# PHOBOS-lbr.net
KiCad netlist of a schematic drawn in EAGLE
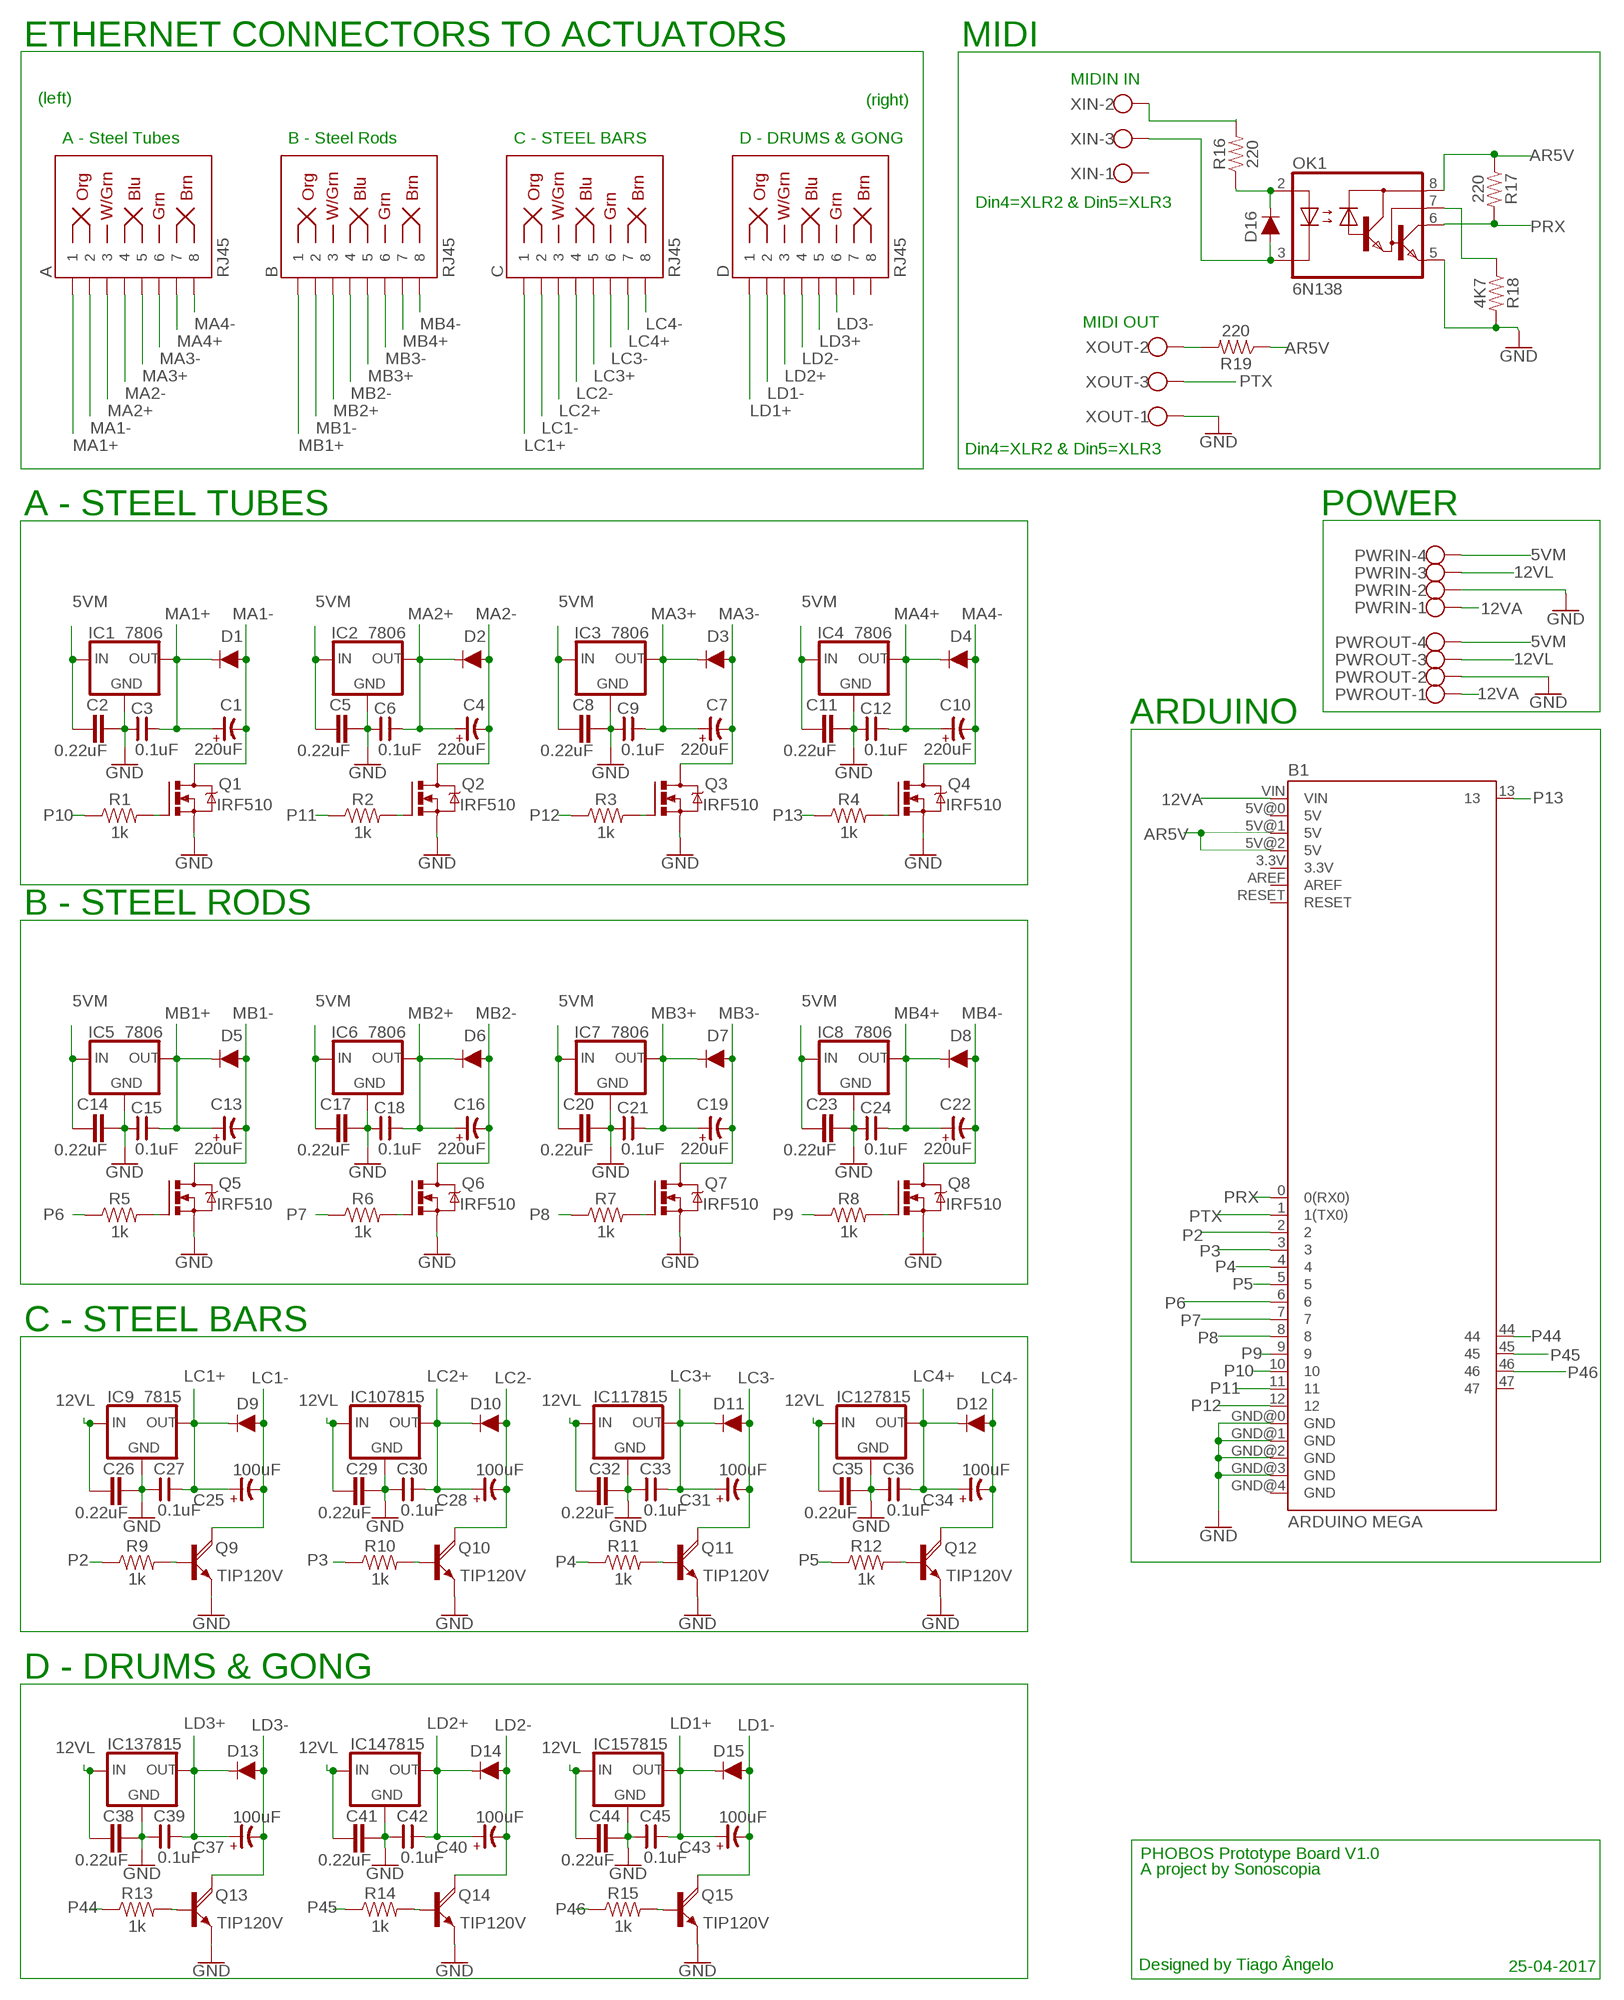
[diagram p0: schematic, sheet 1]

(export (version "E")
  (design (tool "Eeschema 10.0.6"))
  (components
    (comp (ref "A")
      (value "RJ45")
      (footprint "eagle-import:RJ45-8")
      (libsource (lib "eagle-import") (part "RJ45-8"))
    )
    (comp (ref "B")
      (value "RJ45")
      (footprint "eagle-import:RJ45-8")
      (libsource (lib "eagle-import") (part "RJ45-8"))
    )
    (comp (ref "B1")
      (value "ARDUINO MEGA")
      (footprint "eagle-import:ARDUINO_MEGA")
      (libsource (lib "eagle-import") (part "ARDUINO_MEGA_R3FULL"))
    )
    (comp (ref "C")
      (value "RJ45")
      (footprint "eagle-import:RJ45-8")
      (libsource (lib "eagle-import") (part "RJ45-8"))
    )
    (comp (ref "C1")
      (value "220uF")
      (footprint "eagle-import:E-035X080")
      (libsource (lib "eagle-import") (part "CP-E-035X080"))
    )
    (comp (ref "C2")
      (value "0.22uF")
      (footprint "eagle-import:C5B3")
      (libsource (lib "eagle-import") (part "C5/3"))
    )
    (comp (ref "C3")
      (value "0.1uF")
      (footprint "eagle-import:C025-050X025")
      (libsource (lib "eagle-import") (part "CNP-C025-050X025"))
    )
    (comp (ref "C4")
      (value "220uF")
      (footprint "eagle-import:E-035X080")
      (libsource (lib "eagle-import") (part "CP-E-035X080"))
    )
    (comp (ref "C5")
      (value "0.22uF")
      (footprint "eagle-import:C5B3")
      (libsource (lib "eagle-import") (part "C5/3"))
    )
    (comp (ref "C6")
      (value "0.1uF")
      (footprint "eagle-import:C025-050X025")
      (libsource (lib "eagle-import") (part "CNP-C025-050X025"))
    )
    (comp (ref "C7")
      (value "220uF")
      (footprint "eagle-import:E-035X080")
      (libsource (lib "eagle-import") (part "CP-E-035X080"))
    )
    (comp (ref "C8")
      (value "0.22uF")
      (footprint "eagle-import:C5B3")
      (libsource (lib "eagle-import") (part "C5/3"))
    )
    (comp (ref "C9")
      (value "0.1uF")
      (footprint "eagle-import:C025-050X025")
      (libsource (lib "eagle-import") (part "CNP-C025-050X025"))
    )
    (comp (ref "C10")
      (value "220uF")
      (footprint "eagle-import:E-035X080")
      (libsource (lib "eagle-import") (part "CP-E-035X080"))
    )
    (comp (ref "C11")
      (value "0.22uF")
      (footprint "eagle-import:C5B3")
      (libsource (lib "eagle-import") (part "C5/3"))
    )
    (comp (ref "C12")
      (value "0.1uF")
      (footprint "eagle-import:C025-050X025")
      (libsource (lib "eagle-import") (part "CNP-C025-050X025"))
    )
    (comp (ref "C13")
      (value "220uF")
      (footprint "eagle-import:E-035X080")
      (libsource (lib "eagle-import") (part "CP-E-035X080"))
    )
    (comp (ref "C14")
      (value "0.22uF")
      (footprint "eagle-import:C5B3")
      (libsource (lib "eagle-import") (part "C5/3"))
    )
    (comp (ref "C15")
      (value "0.1uF")
      (footprint "eagle-import:C025-050X025")
      (libsource (lib "eagle-import") (part "CNP-C025-050X025"))
    )
    (comp (ref "C16")
      (value "220uF")
      (footprint "eagle-import:E-035X080")
      (libsource (lib "eagle-import") (part "CP-E-035X080"))
    )
    (comp (ref "C17")
      (value "0.22uF")
      (footprint "eagle-import:C5B3")
      (libsource (lib "eagle-import") (part "C5/3"))
    )
    (comp (ref "C18")
      (value "0.1uF")
      (footprint "eagle-import:C025-050X025")
      (libsource (lib "eagle-import") (part "CNP-C025-050X025"))
    )
    (comp (ref "C19")
      (value "220uF")
      (footprint "eagle-import:E-035X080")
      (libsource (lib "eagle-import") (part "CP-E-035X080"))
    )
    (comp (ref "C20")
      (value "0.22uF")
      (footprint "eagle-import:C5B3")
      (libsource (lib "eagle-import") (part "C5/3"))
    )
    (comp (ref "C21")
      (value "0.1uF")
      (footprint "eagle-import:C025-050X025")
      (libsource (lib "eagle-import") (part "CNP-C025-050X025"))
    )
    (comp (ref "C22")
      (value "220uF")
      (footprint "eagle-import:E-035X080")
      (libsource (lib "eagle-import") (part "CP-E-035X080"))
    )
    (comp (ref "C23")
      (value "0.22uF")
      (footprint "eagle-import:C5B3")
      (libsource (lib "eagle-import") (part "C5/3"))
    )
    (comp (ref "C24")
      (value "0.1uF")
      (footprint "eagle-import:C025-050X025")
      (libsource (lib "eagle-import") (part "CNP-C025-050X025"))
    )
    (comp (ref "C25")
      (value "100uF")
      (footprint "eagle-import:E-020X050")
      (libsource (lib "eagle-import") (part "CP-E-020X050"))
    )
    (comp (ref "C26")
      (value "0.22uF")
      (footprint "eagle-import:C5B3")
      (libsource (lib "eagle-import") (part "C5/3"))
    )
    (comp (ref "C27")
      (value "0.1uF")
      (footprint "eagle-import:C025-050X025")
      (libsource (lib "eagle-import") (part "CNP-C025-050X025"))
    )
    (comp (ref "C28")
      (value "100uF")
      (footprint "eagle-import:E-020X050")
      (libsource (lib "eagle-import") (part "CP-E-020X050"))
    )
    (comp (ref "C29")
      (value "0.22uF")
      (footprint "eagle-import:C5B3")
      (libsource (lib "eagle-import") (part "C5/3"))
    )
    (comp (ref "C30")
      (value "0.1uF")
      (footprint "eagle-import:C025-050X025")
      (libsource (lib "eagle-import") (part "CNP-C025-050X025"))
    )
    (comp (ref "C31")
      (value "100uF")
      (footprint "eagle-import:E-020X050")
      (libsource (lib "eagle-import") (part "CP-E-020X050"))
    )
    (comp (ref "C32")
      (value "0.22uF")
      (footprint "eagle-import:C5B3")
      (libsource (lib "eagle-import") (part "C5/3"))
    )
    (comp (ref "C33")
      (value "0.1uF")
      (footprint "eagle-import:C025-050X025")
      (libsource (lib "eagle-import") (part "CNP-C025-050X025"))
    )
    (comp (ref "C34")
      (value "100uF")
      (footprint "eagle-import:E-020X050")
      (libsource (lib "eagle-import") (part "CP-E-020X050"))
    )
    (comp (ref "C35")
      (value "0.22uF")
      (footprint "eagle-import:C5B3")
      (libsource (lib "eagle-import") (part "C5/3"))
    )
    (comp (ref "C36")
      (value "0.1uF")
      (footprint "eagle-import:C025-050X025")
      (libsource (lib "eagle-import") (part "CNP-C025-050X025"))
    )
    (comp (ref "C37")
      (value "100uF")
      (footprint "eagle-import:E-020X050")
      (libsource (lib "eagle-import") (part "CP-E-020X050"))
    )
    (comp (ref "C38")
      (value "0.22uF")
      (footprint "eagle-import:C5B3")
      (libsource (lib "eagle-import") (part "C5/3"))
    )
    (comp (ref "C39")
      (value "0.1uF")
      (footprint "eagle-import:C025-050X025")
      (libsource (lib "eagle-import") (part "CNP-C025-050X025"))
    )
    (comp (ref "C40")
      (value "100uF")
      (footprint "eagle-import:E-020X050")
      (libsource (lib "eagle-import") (part "CP-E-020X050"))
    )
    (comp (ref "C41")
      (value "0.22uF")
      (footprint "eagle-import:C5B3")
      (libsource (lib "eagle-import") (part "C5/3"))
    )
    (comp (ref "C42")
      (value "0.1uF")
      (footprint "eagle-import:C025-050X025")
      (libsource (lib "eagle-import") (part "CNP-C025-050X025"))
    )
    (comp (ref "C43")
      (value "100uF")
      (footprint "eagle-import:E-020X050")
      (libsource (lib "eagle-import") (part "CP-E-020X050"))
    )
    (comp (ref "C44")
      (value "0.22uF")
      (footprint "eagle-import:C5B3")
      (libsource (lib "eagle-import") (part "C5/3"))
    )
    (comp (ref "C45")
      (value "0.1uF")
      (footprint "eagle-import:C025-050X025")
      (libsource (lib "eagle-import") (part "CNP-C025-050X025"))
    )
    (comp (ref "D")
      (value "RJ45")
      (footprint "eagle-import:RJ45-8")
      (libsource (lib "eagle-import") (part "RJ45-8"))
    )
    (comp (ref "D1")
      (value "1A/50V/1.1V")
      (footprint "eagle-import:DIODE-1N4001-KIT")
      (libsource (lib "eagle-import") (part "DIODE-KIT2"))
    )
    (comp (ref "D2")
      (value "1A/50V/1.1V")
      (footprint "eagle-import:DIODE-1N4001-KIT")
      (libsource (lib "eagle-import") (part "DIODE-KIT2"))
    )
    (comp (ref "D3")
      (value "1A/50V/1.1V")
      (footprint "eagle-import:DIODE-1N4001-KIT")
      (libsource (lib "eagle-import") (part "DIODE-KIT2"))
    )
    (comp (ref "D4")
      (value "1A/50V/1.1V")
      (footprint "eagle-import:DIODE-1N4001-KIT")
      (libsource (lib "eagle-import") (part "DIODE-KIT2"))
    )
    (comp (ref "D5")
      (value "1A/50V/1.1V")
      (footprint "eagle-import:DIODE-1N4001-KIT")
      (libsource (lib "eagle-import") (part "DIODE-KIT2"))
    )
    (comp (ref "D6")
      (value "1A/50V/1.1V")
      (footprint "eagle-import:DIODE-1N4001-KIT")
      (libsource (lib "eagle-import") (part "DIODE-KIT2"))
    )
    (comp (ref "D7")
      (value "1A/50V/1.1V")
      (footprint "eagle-import:DIODE-1N4001-KIT")
      (libsource (lib "eagle-import") (part "DIODE-KIT2"))
    )
    (comp (ref "D8")
      (value "1A/50V/1.1V")
      (footprint "eagle-import:DIODE-1N4001-KIT")
      (libsource (lib "eagle-import") (part "DIODE-KIT2"))
    )
    (comp (ref "D9")
      (value "1A/50V/1.1V")
      (footprint "eagle-import:DIODE-1N4001-KIT")
      (libsource (lib "eagle-import") (part "DIODE-KIT2"))
    )
    (comp (ref "D10")
      (value "1A/50V/1.1V")
      (footprint "eagle-import:DIODE-1N4001-KIT")
      (libsource (lib "eagle-import") (part "DIODE-KIT2"))
    )
    (comp (ref "D11")
      (value "1A/50V/1.1V")
      (footprint "eagle-import:DIODE-1N4001-KIT")
      (libsource (lib "eagle-import") (part "DIODE-KIT2"))
    )
    (comp (ref "D12")
      (value "1A/50V/1.1V")
      (footprint "eagle-import:DIODE-1N4001-KIT")
      (libsource (lib "eagle-import") (part "DIODE-KIT2"))
    )
    (comp (ref "D13")
      (value "1A/50V/1.1V")
      (footprint "eagle-import:DIODE-1N4001-KIT")
      (libsource (lib "eagle-import") (part "DIODE-KIT2"))
    )
    (comp (ref "D14")
      (value "1A/50V/1.1V")
      (footprint "eagle-import:DIODE-1N4001-KIT")
      (libsource (lib "eagle-import") (part "DIODE-KIT2"))
    )
    (comp (ref "D15")
      (value "1A/50V/1.1V")
      (footprint "eagle-import:DIODE-1N4001-KIT")
      (libsource (lib "eagle-import") (part "DIODE-KIT2"))
    )
    (comp (ref "D16")
      (value "200mA/100V/1V")
      (footprint "eagle-import:DIODE-1N4148")
      (libsource (lib "eagle-import") (part "DIODE-1N4148"))
    )
    (comp (ref "IC1")
      (value "7806")
      (footprint "eagle-import:78XXS")
      (libsource (lib "eagle-import") (part "78XXS"))
    )
    (comp (ref "IC2")
      (value "7806")
      (footprint "eagle-import:78XXS")
      (libsource (lib "eagle-import") (part "78XXS"))
    )
    (comp (ref "IC3")
      (value "7806")
      (footprint "eagle-import:78XXS")
      (libsource (lib "eagle-import") (part "78XXS"))
    )
    (comp (ref "IC4")
      (value "7806")
      (footprint "eagle-import:78XXS")
      (libsource (lib "eagle-import") (part "78XXS"))
    )
    (comp (ref "IC5")
      (value "7806")
      (footprint "eagle-import:78XXS")
      (libsource (lib "eagle-import") (part "78XXS"))
    )
    (comp (ref "IC6")
      (value "7806")
      (footprint "eagle-import:78XXS")
      (libsource (lib "eagle-import") (part "78XXS"))
    )
    (comp (ref "IC7")
      (value "7806")
      (footprint "eagle-import:78XXS")
      (libsource (lib "eagle-import") (part "78XXS"))
    )
    (comp (ref "IC8")
      (value "7806")
      (footprint "eagle-import:78XXS")
      (libsource (lib "eagle-import") (part "78XXS"))
    )
    (comp (ref "IC9")
      (value "7815")
      (footprint "eagle-import:78XXS")
      (libsource (lib "eagle-import") (part "78XXS"))
    )
    (comp (ref "IC10")
      (value "7815")
      (footprint "eagle-import:78XXS")
      (libsource (lib "eagle-import") (part "78XXS"))
    )
    (comp (ref "IC11")
      (value "7815")
      (footprint "eagle-import:78XXS")
      (libsource (lib "eagle-import") (part "78XXS"))
    )
    (comp (ref "IC12")
      (value "7815")
      (footprint "eagle-import:78XXS")
      (libsource (lib "eagle-import") (part "78XXS"))
    )
    (comp (ref "IC13")
      (value "7815")
      (footprint "eagle-import:78XXS")
      (libsource (lib "eagle-import") (part "78XXS"))
    )
    (comp (ref "IC14")
      (value "7815")
      (footprint "eagle-import:78XXS")
      (libsource (lib "eagle-import") (part "78XXS"))
    )
    (comp (ref "IC15")
      (value "7815")
      (footprint "eagle-import:78XXS")
      (libsource (lib "eagle-import") (part "78XXS"))
    )
    (comp (ref "OK1")
      (value "6N138")
      (footprint "eagle-import:DIL08")
      (fields (field (name "MF") "VISHAY/TELEFUNKEN"))
      (libsource (lib "eagle-import") (part "6N138"))
    )
    (comp (ref "PWRIN")
      (value "W237-4")
      (footprint "eagle-import:W237-4")
      (libsource (lib "eagle-import") (part "W237-4"))
    )
    (comp (ref "PWROUT")
      (value "W237-4")
      (footprint "eagle-import:W237-4")
      (libsource (lib "eagle-import") (part "W237-4"))
    )
    (comp (ref "Q1")
      (value "IRF510")
      (footprint "eagle-import:TO220BV")
      (libsource (lib "eagle-import") (part "IRF520"))
    )
    (comp (ref "Q2")
      (value "IRF510")
      (footprint "eagle-import:TO220BV")
      (libsource (lib "eagle-import") (part "IRF520"))
    )
    (comp (ref "Q3")
      (value "IRF510")
      (footprint "eagle-import:TO220BV")
      (libsource (lib "eagle-import") (part "IRF520"))
    )
    (comp (ref "Q4")
      (value "IRF510")
      (footprint "eagle-import:TO220BV")
      (libsource (lib "eagle-import") (part "IRF520"))
    )
    (comp (ref "Q5")
      (value "IRF510")
      (footprint "eagle-import:TO220BV")
      (libsource (lib "eagle-import") (part "IRF520"))
    )
    (comp (ref "Q6")
      (value "IRF510")
      (footprint "eagle-import:TO220BV")
      (libsource (lib "eagle-import") (part "IRF520"))
    )
    (comp (ref "Q7")
      (value "IRF510")
      (footprint "eagle-import:TO220BV")
      (libsource (lib "eagle-import") (part "IRF520"))
    )
    (comp (ref "Q8")
      (value "IRF510")
      (footprint "eagle-import:TO220BV")
      (libsource (lib "eagle-import") (part "IRF520"))
    )
    (comp (ref "Q9")
      (value "TIP120V")
      (footprint "eagle-import:TO220AV")
      (libsource (lib "eagle-import") (part "TIP120V"))
    )
    (comp (ref "Q10")
      (value "TIP120V")
      (footprint "eagle-import:TO220AV")
      (libsource (lib "eagle-import") (part "TIP120V"))
    )
    (comp (ref "Q11")
      (value "TIP120V")
      (footprint "eagle-import:TO220AV")
      (libsource (lib "eagle-import") (part "TIP120V"))
    )
    (comp (ref "Q12")
      (value "TIP120V")
      (footprint "eagle-import:TO220AV")
      (libsource (lib "eagle-import") (part "TIP120V"))
    )
    (comp (ref "Q13")
      (value "TIP120V")
      (footprint "eagle-import:TO220AV")
      (libsource (lib "eagle-import") (part "TIP120V"))
    )
    (comp (ref "Q14")
      (value "TIP120V")
      (footprint "eagle-import:TO220AV")
      (libsource (lib "eagle-import") (part "TIP120V"))
    )
    (comp (ref "Q15")
      (value "TIP120V")
      (footprint "eagle-import:TO220AV")
      (libsource (lib "eagle-import") (part "TIP120V"))
    )
    (comp (ref "R1")
      (value "1k")
      (footprint "eagle-import:AXIAL-0.1")
      (libsource (lib "eagle-import") (part "1KOHM-VERT-1/4W-1%"))
    )
    (comp (ref "R2")
      (value "1k")
      (footprint "eagle-import:AXIAL-0.1")
      (libsource (lib "eagle-import") (part "1KOHM-VERT-1/4W-1%"))
    )
    (comp (ref "R3")
      (value "1k")
      (footprint "eagle-import:AXIAL-0.1")
      (libsource (lib "eagle-import") (part "1KOHM-VERT-1/4W-1%"))
    )
    (comp (ref "R4")
      (value "1k")
      (footprint "eagle-import:AXIAL-0.1")
      (libsource (lib "eagle-import") (part "1KOHM-VERT-1/4W-1%"))
    )
    (comp (ref "R5")
      (value "1k")
      (footprint "eagle-import:AXIAL-0.1")
      (libsource (lib "eagle-import") (part "1KOHM-VERT-1/4W-1%"))
    )
    (comp (ref "R6")
      (value "1k")
      (footprint "eagle-import:AXIAL-0.1")
      (libsource (lib "eagle-import") (part "1KOHM-VERT-1/4W-1%"))
    )
    (comp (ref "R7")
      (value "1k")
      (footprint "eagle-import:AXIAL-0.1")
      (libsource (lib "eagle-import") (part "1KOHM-VERT-1/4W-1%"))
    )
    (comp (ref "R8")
      (value "1k")
      (footprint "eagle-import:AXIAL-0.1")
      (libsource (lib "eagle-import") (part "1KOHM-VERT-1/4W-1%"))
    )
    (comp (ref "R9")
      (value "1k")
      (footprint "eagle-import:AXIAL-0.1")
      (libsource (lib "eagle-import") (part "1KOHM-VERT-1/4W-1%"))
    )
    (comp (ref "R10")
      (value "1k")
      (footprint "eagle-import:AXIAL-0.1")
      (libsource (lib "eagle-import") (part "1KOHM-VERT-1/4W-1%"))
    )
    (comp (ref "R11")
      (value "1k")
      (footprint "eagle-import:AXIAL-0.1")
      (libsource (lib "eagle-import") (part "1KOHM-VERT-1/4W-1%"))
    )
    (comp (ref "R12")
      (value "1k")
      (footprint "eagle-import:AXIAL-0.1")
      (libsource (lib "eagle-import") (part "1KOHM-VERT-1/4W-1%"))
    )
    (comp (ref "R13")
      (value "1k")
      (footprint "eagle-import:AXIAL-0.1")
      (libsource (lib "eagle-import") (part "1KOHM-VERT-1/4W-1%"))
    )
    (comp (ref "R14")
      (value "1k")
      (footprint "eagle-import:AXIAL-0.1")
      (libsource (lib "eagle-import") (part "1KOHM-VERT-1/4W-1%"))
    )
    (comp (ref "R15")
      (value "1k")
      (footprint "eagle-import:AXIAL-0.1")
      (libsource (lib "eagle-import") (part "1KOHM-VERT-1/4W-1%"))
    )
    (comp (ref "R16")
      (value "220")
      (footprint "eagle-import:AXIAL-0.3")
      (libsource (lib "eagle-import") (part "1KOHM-HORIZ-1/4W-5%"))
    )
    (comp (ref "R17")
      (value "220")
      (footprint "eagle-import:AXIAL-0.3")
      (libsource (lib "eagle-import") (part "1KOHM-HORIZ-1/4W-5%"))
    )
    (comp (ref "R18")
      (value "4K7")
      (footprint "eagle-import:AXIAL-0.3")
      (libsource (lib "eagle-import") (part "1KOHM-HORIZ-1/4W-5%"))
    )
    (comp (ref "R19")
      (value "220")
      (footprint "eagle-import:AXIAL-0.3")
      (libsource (lib "eagle-import") (part "1KOHM-HORIZ-1/4W-5%"))
    )
    (comp (ref "XIN")
      (value "W237-103")
      (footprint "eagle-import:W237-103")
      (fields (field (name "MPN") "237-103"))
      (libsource (lib "eagle-import") (part "W237-103"))
    )
    (comp (ref "XOUT")
      (value "W237-103")
      (footprint "eagle-import:W237-103")
      (fields (field (name "MPN") "237-103"))
      (libsource (lib "eagle-import") (part "W237-103"))
    )
  )
  (nets
    (net (code "1") (name "/5VM") (class "Default")
      (node (ref "C11") (pin "1") (pinfunction "1_1") (pintype "passive"))
      (node (ref "C14") (pin "1") (pinfunction "1_1") (pintype "passive"))
      (node (ref "C17") (pin "1") (pinfunction "1_1") (pintype "passive"))
      (node (ref "C2") (pin "1") (pinfunction "1_1") (pintype "passive"))
      (node (ref "C20") (pin "1") (pinfunction "1_1") (pintype "passive"))
      (node (ref "C23") (pin "1") (pinfunction "1_1") (pintype "passive"))
      (node (ref "C5") (pin "1") (pinfunction "1_1") (pintype "passive"))
      (node (ref "C8") (pin "1") (pinfunction "1_1") (pintype "passive"))
      (node (ref "IC1") (pin "IN") (pinfunction "IN_IN") (pintype "input"))
      (node (ref "IC2") (pin "IN") (pinfunction "IN_IN") (pintype "input"))
      (node (ref "IC3") (pin "IN") (pinfunction "IN_IN") (pintype "input"))
      (node (ref "IC4") (pin "IN") (pinfunction "IN_IN") (pintype "input"))
      (node (ref "IC5") (pin "IN") (pinfunction "IN_IN") (pintype "input"))
      (node (ref "IC6") (pin "IN") (pinfunction "IN_IN") (pintype "input"))
      (node (ref "IC7") (pin "IN") (pinfunction "IN_IN") (pintype "input"))
      (node (ref "IC8") (pin "IN") (pinfunction "IN_IN") (pintype "input"))
      (node (ref "PWRIN") (pin "4") (pinfunction "KL_4") (pintype "passive"))
      (node (ref "PWROUT") (pin "4") (pinfunction "KL_4") (pintype "passive"))
    )
    (net (code "2") (name "/12VA") (class "Default")
      (node (ref "B1") (pin "VIN") (pinfunction "VIN_VIN") (pintype "bidirectional"))
      (node (ref "PWRIN") (pin "1") (pinfunction "KL_1") (pintype "passive"))
      (node (ref "PWROUT") (pin "1") (pinfunction "KL_1") (pintype "passive"))
    )
    (net (code "3") (name "/12VL") (class "Default")
      (node (ref "C26") (pin "1") (pinfunction "1_1") (pintype "passive"))
      (node (ref "C29") (pin "1") (pinfunction "1_1") (pintype "passive"))
      (node (ref "C32") (pin "1") (pinfunction "1_1") (pintype "passive"))
      (node (ref "C35") (pin "1") (pinfunction "1_1") (pintype "passive"))
      (node (ref "C38") (pin "1") (pinfunction "1_1") (pintype "passive"))
      (node (ref "C41") (pin "1") (pinfunction "1_1") (pintype "passive"))
      (node (ref "C44") (pin "1") (pinfunction "1_1") (pintype "passive"))
      (node (ref "IC10") (pin "IN") (pinfunction "IN_IN") (pintype "input"))
      (node (ref "IC11") (pin "IN") (pinfunction "IN_IN") (pintype "input"))
      (node (ref "IC12") (pin "IN") (pinfunction "IN_IN") (pintype "input"))
      (node (ref "IC13") (pin "IN") (pinfunction "IN_IN") (pintype "input"))
      (node (ref "IC14") (pin "IN") (pinfunction "IN_IN") (pintype "input"))
      (node (ref "IC15") (pin "IN") (pinfunction "IN_IN") (pintype "input"))
      (node (ref "IC9") (pin "IN") (pinfunction "IN_IN") (pintype "input"))
      (node (ref "PWRIN") (pin "3") (pinfunction "KL_3") (pintype "passive"))
      (node (ref "PWROUT") (pin "3") (pinfunction "KL_3") (pintype "passive"))
    )
    (net (code "4") (name "/AR5V") (class "Default")
      (node (ref "B1") (pin "5V@1") (pinfunction "5V_5V@1") (pintype "bidirectional"))
      (node (ref "B1") (pin "5V@2") (pinfunction "5V_5V@2") (pintype "bidirectional"))
      (node (ref "OK1") (pin "8") (pinfunction "VCC_8") (pintype "passive"))
      (node (ref "R17") (pin "P$1") (pinfunction "1_P$1") (pintype "passive"))
      (node (ref "R19") (pin "P$1") (pinfunction "1_P$1") (pintype "passive"))
    )
    (net (code "5") (name "/LC1+") (class "Default")
      (node (ref "C") (pin "1") (pinfunction "1_1") (pintype "bidirectional"))
      (node (ref "C25") (pin "+") (pinfunction "+_+") (pintype "passive"))
      (node (ref "C27") (pin "2") (pinfunction "2_2") (pintype "passive"))
      (node (ref "D9") (pin "C") (pinfunction "C_C") (pintype "passive"))
      (node (ref "IC9") (pin "OUT") (pinfunction "OUT_OUT") (pintype "passive"))
    )
    (net (code "6") (name "/LC1-") (class "Default")
      (node (ref "C") (pin "2") (pinfunction "2_2") (pintype "bidirectional"))
      (node (ref "C25") (pin "-") (pinfunction "-_-") (pintype "passive"))
      (node (ref "D9") (pin "A") (pinfunction "A_A") (pintype "passive"))
      (node (ref "Q9") (pin "C") (pinfunction "C_C") (pintype "passive"))
    )
    (net (code "7") (name "/LC2+") (class "Default")
      (node (ref "C") (pin "3") (pinfunction "3_3") (pintype "bidirectional"))
      (node (ref "C28") (pin "+") (pinfunction "+_+") (pintype "passive"))
      (node (ref "C30") (pin "2") (pinfunction "2_2") (pintype "passive"))
      (node (ref "D10") (pin "C") (pinfunction "C_C") (pintype "passive"))
      (node (ref "IC10") (pin "OUT") (pinfunction "OUT_OUT") (pintype "passive"))
    )
    (net (code "8") (name "/LC2-") (class "Default")
      (node (ref "C") (pin "4") (pinfunction "4_4") (pintype "bidirectional"))
      (node (ref "C28") (pin "-") (pinfunction "-_-") (pintype "passive"))
      (node (ref "D10") (pin "A") (pinfunction "A_A") (pintype "passive"))
      (node (ref "Q10") (pin "C") (pinfunction "C_C") (pintype "passive"))
    )
    (net (code "9") (name "/LC3+") (class "Default")
      (node (ref "C") (pin "5") (pinfunction "5_5") (pintype "bidirectional"))
      (node (ref "C31") (pin "+") (pinfunction "+_+") (pintype "passive"))
      (node (ref "C33") (pin "2") (pinfunction "2_2") (pintype "passive"))
      (node (ref "D11") (pin "C") (pinfunction "C_C") (pintype "passive"))
      (node (ref "IC11") (pin "OUT") (pinfunction "OUT_OUT") (pintype "passive"))
    )
    (net (code "10") (name "/LC3-") (class "Default")
      (node (ref "C") (pin "6") (pinfunction "6_6") (pintype "bidirectional"))
      (node (ref "C31") (pin "-") (pinfunction "-_-") (pintype "passive"))
      (node (ref "D11") (pin "A") (pinfunction "A_A") (pintype "passive"))
      (node (ref "Q11") (pin "C") (pinfunction "C_C") (pintype "passive"))
    )
    (net (code "11") (name "/LC4+") (class "Default")
      (node (ref "C") (pin "7") (pinfunction "7_7") (pintype "bidirectional"))
      (node (ref "C34") (pin "+") (pinfunction "+_+") (pintype "passive"))
      (node (ref "C36") (pin "2") (pinfunction "2_2") (pintype "passive"))
      (node (ref "D12") (pin "C") (pinfunction "C_C") (pintype "passive"))
      (node (ref "IC12") (pin "OUT") (pinfunction "OUT_OUT") (pintype "passive"))
    )
    (net (code "12") (name "/LC4-") (class "Default")
      (node (ref "C") (pin "8") (pinfunction "8_8") (pintype "bidirectional"))
      (node (ref "C34") (pin "-") (pinfunction "-_-") (pintype "passive"))
      (node (ref "D12") (pin "A") (pinfunction "A_A") (pintype "passive"))
      (node (ref "Q12") (pin "C") (pinfunction "C_C") (pintype "passive"))
    )
    (net (code "13") (name "/LD1+") (class "Default")
      (node (ref "C43") (pin "+") (pinfunction "+_+") (pintype "passive"))
      (node (ref "C45") (pin "2") (pinfunction "2_2") (pintype "passive"))
      (node (ref "D") (pin "1") (pinfunction "1_1") (pintype "bidirectional"))
      (node (ref "D15") (pin "C") (pinfunction "C_C") (pintype "passive"))
      (node (ref "IC15") (pin "OUT") (pinfunction "OUT_OUT") (pintype "passive"))
    )
    (net (code "14") (name "/LD1-") (class "Default")
      (node (ref "C43") (pin "-") (pinfunction "-_-") (pintype "passive"))
      (node (ref "D") (pin "2") (pinfunction "2_2") (pintype "bidirectional"))
      (node (ref "D15") (pin "A") (pinfunction "A_A") (pintype "passive"))
      (node (ref "Q15") (pin "C") (pinfunction "C_C") (pintype "passive"))
    )
    (net (code "15") (name "/LD2+") (class "Default")
      (node (ref "C40") (pin "+") (pinfunction "+_+") (pintype "passive"))
      (node (ref "C42") (pin "2") (pinfunction "2_2") (pintype "passive"))
      (node (ref "D") (pin "3") (pinfunction "3_3") (pintype "bidirectional"))
      (node (ref "D14") (pin "C") (pinfunction "C_C") (pintype "passive"))
      (node (ref "IC14") (pin "OUT") (pinfunction "OUT_OUT") (pintype "passive"))
    )
    (net (code "16") (name "/LD2-") (class "Default")
      (node (ref "C40") (pin "-") (pinfunction "-_-") (pintype "passive"))
      (node (ref "D") (pin "4") (pinfunction "4_4") (pintype "bidirectional"))
      (node (ref "D14") (pin "A") (pinfunction "A_A") (pintype "passive"))
      (node (ref "Q14") (pin "C") (pinfunction "C_C") (pintype "passive"))
    )
    (net (code "17") (name "/LD3+") (class "Default")
      (node (ref "C37") (pin "+") (pinfunction "+_+") (pintype "passive"))
      (node (ref "C39") (pin "2") (pinfunction "2_2") (pintype "passive"))
      (node (ref "D") (pin "5") (pinfunction "5_5") (pintype "bidirectional"))
      (node (ref "D13") (pin "C") (pinfunction "C_C") (pintype "passive"))
      (node (ref "IC13") (pin "OUT") (pinfunction "OUT_OUT") (pintype "passive"))
    )
    (net (code "18") (name "/LD3-") (class "Default")
      (node (ref "C37") (pin "-") (pinfunction "-_-") (pintype "passive"))
      (node (ref "D") (pin "6") (pinfunction "6_6") (pintype "bidirectional"))
      (node (ref "D13") (pin "A") (pinfunction "A_A") (pintype "passive"))
      (node (ref "Q13") (pin "C") (pinfunction "C_C") (pintype "passive"))
    )
    (net (code "19") (name "/MA1+") (class "Default")
      (node (ref "A") (pin "1") (pinfunction "1_1") (pintype "bidirectional"))
      (node (ref "C1") (pin "+") (pinfunction "+_+") (pintype "passive"))
      (node (ref "C3") (pin "2") (pinfunction "2_2") (pintype "passive"))
      (node (ref "D1") (pin "C") (pinfunction "C_C") (pintype "passive"))
      (node (ref "IC1") (pin "OUT") (pinfunction "OUT_OUT") (pintype "passive"))
    )
    (net (code "20") (name "/MA1-") (class "Default")
      (node (ref "A") (pin "2") (pinfunction "2_2") (pintype "bidirectional"))
      (node (ref "C1") (pin "-") (pinfunction "-_-") (pintype "passive"))
      (node (ref "D1") (pin "A") (pinfunction "A_A") (pintype "passive"))
      (node (ref "Q1") (pin "D") (pinfunction "D_D") (pintype "passive"))
    )
    (net (code "21") (name "/MA2+") (class "Default")
      (node (ref "A") (pin "3") (pinfunction "3_3") (pintype "bidirectional"))
      (node (ref "C4") (pin "+") (pinfunction "+_+") (pintype "passive"))
      (node (ref "C6") (pin "2") (pinfunction "2_2") (pintype "passive"))
      (node (ref "D2") (pin "C") (pinfunction "C_C") (pintype "passive"))
      (node (ref "IC2") (pin "OUT") (pinfunction "OUT_OUT") (pintype "passive"))
    )
    (net (code "22") (name "/MA2-") (class "Default")
      (node (ref "A") (pin "4") (pinfunction "4_4") (pintype "bidirectional"))
      (node (ref "C4") (pin "-") (pinfunction "-_-") (pintype "passive"))
      (node (ref "D2") (pin "A") (pinfunction "A_A") (pintype "passive"))
      (node (ref "Q2") (pin "D") (pinfunction "D_D") (pintype "passive"))
    )
    (net (code "23") (name "/MA3+") (class "Default")
      (node (ref "A") (pin "5") (pinfunction "5_5") (pintype "bidirectional"))
      (node (ref "C7") (pin "+") (pinfunction "+_+") (pintype "passive"))
      (node (ref "C9") (pin "2") (pinfunction "2_2") (pintype "passive"))
      (node (ref "D3") (pin "C") (pinfunction "C_C") (pintype "passive"))
      (node (ref "IC3") (pin "OUT") (pinfunction "OUT_OUT") (pintype "passive"))
    )
    (net (code "24") (name "/MA3-") (class "Default")
      (node (ref "A") (pin "6") (pinfunction "6_6") (pintype "bidirectional"))
      (node (ref "C7") (pin "-") (pinfunction "-_-") (pintype "passive"))
      (node (ref "D3") (pin "A") (pinfunction "A_A") (pintype "passive"))
      (node (ref "Q3") (pin "D") (pinfunction "D_D") (pintype "passive"))
    )
    (net (code "25") (name "/MA4+") (class "Default")
      (node (ref "A") (pin "7") (pinfunction "7_7") (pintype "bidirectional"))
      (node (ref "C10") (pin "+") (pinfunction "+_+") (pintype "passive"))
      (node (ref "C12") (pin "2") (pinfunction "2_2") (pintype "passive"))
      (node (ref "D4") (pin "C") (pinfunction "C_C") (pintype "passive"))
      (node (ref "IC4") (pin "OUT") (pinfunction "OUT_OUT") (pintype "passive"))
    )
    (net (code "26") (name "/MA4-") (class "Default")
      (node (ref "A") (pin "8") (pinfunction "8_8") (pintype "bidirectional"))
      (node (ref "C10") (pin "-") (pinfunction "-_-") (pintype "passive"))
      (node (ref "D4") (pin "A") (pinfunction "A_A") (pintype "passive"))
      (node (ref "Q4") (pin "D") (pinfunction "D_D") (pintype "passive"))
    )
    (net (code "27") (name "/MB1+") (class "Default")
      (node (ref "B") (pin "1") (pinfunction "1_1") (pintype "bidirectional"))
      (node (ref "C13") (pin "+") (pinfunction "+_+") (pintype "passive"))
      (node (ref "C15") (pin "2") (pinfunction "2_2") (pintype "passive"))
      (node (ref "D5") (pin "C") (pinfunction "C_C") (pintype "passive"))
      (node (ref "IC5") (pin "OUT") (pinfunction "OUT_OUT") (pintype "passive"))
    )
    (net (code "28") (name "/MB1-") (class "Default")
      (node (ref "B") (pin "2") (pinfunction "2_2") (pintype "bidirectional"))
      (node (ref "C13") (pin "-") (pinfunction "-_-") (pintype "passive"))
      (node (ref "D5") (pin "A") (pinfunction "A_A") (pintype "passive"))
      (node (ref "Q5") (pin "D") (pinfunction "D_D") (pintype "passive"))
    )
    (net (code "29") (name "/MB2+") (class "Default")
      (node (ref "B") (pin "3") (pinfunction "3_3") (pintype "bidirectional"))
      (node (ref "C16") (pin "+") (pinfunction "+_+") (pintype "passive"))
      (node (ref "C18") (pin "2") (pinfunction "2_2") (pintype "passive"))
      (node (ref "D6") (pin "C") (pinfunction "C_C") (pintype "passive"))
      (node (ref "IC6") (pin "OUT") (pinfunction "OUT_OUT") (pintype "passive"))
    )
    (net (code "30") (name "/MB2-") (class "Default")
      (node (ref "B") (pin "4") (pinfunction "4_4") (pintype "bidirectional"))
      (node (ref "C16") (pin "-") (pinfunction "-_-") (pintype "passive"))
      (node (ref "D6") (pin "A") (pinfunction "A_A") (pintype "passive"))
      (node (ref "Q6") (pin "D") (pinfunction "D_D") (pintype "passive"))
    )
    (net (code "31") (name "/MB3+") (class "Default")
      (node (ref "B") (pin "5") (pinfunction "5_5") (pintype "bidirectional"))
      (node (ref "C19") (pin "+") (pinfunction "+_+") (pintype "passive"))
      (node (ref "C21") (pin "2") (pinfunction "2_2") (pintype "passive"))
      (node (ref "D7") (pin "C") (pinfunction "C_C") (pintype "passive"))
      (node (ref "IC7") (pin "OUT") (pinfunction "OUT_OUT") (pintype "passive"))
    )
    (net (code "32") (name "/MB3-") (class "Default")
      (node (ref "B") (pin "6") (pinfunction "6_6") (pintype "bidirectional"))
      (node (ref "C19") (pin "-") (pinfunction "-_-") (pintype "passive"))
      (node (ref "D7") (pin "A") (pinfunction "A_A") (pintype "passive"))
      (node (ref "Q7") (pin "D") (pinfunction "D_D") (pintype "passive"))
    )
    (net (code "33") (name "/MB4+") (class "Default")
      (node (ref "B") (pin "7") (pinfunction "7_7") (pintype "bidirectional"))
      (node (ref "C22") (pin "+") (pinfunction "+_+") (pintype "passive"))
      (node (ref "C24") (pin "2") (pinfunction "2_2") (pintype "passive"))
      (node (ref "D8") (pin "C") (pinfunction "C_C") (pintype "passive"))
      (node (ref "IC8") (pin "OUT") (pinfunction "OUT_OUT") (pintype "passive"))
    )
    (net (code "34") (name "/MB4-") (class "Default")
      (node (ref "B") (pin "8") (pinfunction "8_8") (pintype "bidirectional"))
      (node (ref "C22") (pin "-") (pinfunction "-_-") (pintype "passive"))
      (node (ref "D8") (pin "A") (pinfunction "A_A") (pintype "passive"))
      (node (ref "Q8") (pin "D") (pinfunction "D_D") (pintype "passive"))
    )
    (net (code "35") (name "/P2") (class "Default")
      (node (ref "B1") (pin "2") (pinfunction "2_2") (pintype "bidirectional"))
      (node (ref "R9") (pin "P$1") (pinfunction "1_P$1") (pintype "passive"))
    )
    (net (code "36") (name "/P3") (class "Default")
      (node (ref "B1") (pin "3") (pinfunction "3_3") (pintype "bidirectional"))
      (node (ref "R10") (pin "P$1") (pinfunction "1_P$1") (pintype "passive"))
    )
    (net (code "37") (name "/P4") (class "Default")
      (node (ref "B1") (pin "4") (pinfunction "4_4") (pintype "bidirectional"))
      (node (ref "R11") (pin "P$1") (pinfunction "1_P$1") (pintype "passive"))
    )
    (net (code "38") (name "/P5") (class "Default")
      (node (ref "B1") (pin "5") (pinfunction "5_5") (pintype "bidirectional"))
      (node (ref "R12") (pin "P$1") (pinfunction "1_P$1") (pintype "passive"))
    )
    (net (code "39") (name "/P6") (class "Default")
      (node (ref "B1") (pin "6") (pinfunction "6_6") (pintype "bidirectional"))
      (node (ref "R5") (pin "P$1") (pinfunction "1_P$1") (pintype "passive"))
    )
    (net (code "40") (name "/P7") (class "Default")
      (node (ref "B1") (pin "7") (pinfunction "7_7") (pintype "bidirectional"))
      (node (ref "R6") (pin "P$1") (pinfunction "1_P$1") (pintype "passive"))
    )
    (net (code "41") (name "/P8") (class "Default")
      (node (ref "B1") (pin "8") (pinfunction "8_8") (pintype "bidirectional"))
      (node (ref "R7") (pin "P$1") (pinfunction "1_P$1") (pintype "passive"))
    )
    (net (code "42") (name "/P9") (class "Default")
      (node (ref "B1") (pin "9") (pinfunction "9_9") (pintype "bidirectional"))
      (node (ref "R8") (pin "P$1") (pinfunction "1_P$1") (pintype "passive"))
    )
    (net (code "43") (name "/P10") (class "Default")
      (node (ref "B1") (pin "10") (pinfunction "10_10") (pintype "bidirectional"))
      (node (ref "R1") (pin "P$1") (pinfunction "1_P$1") (pintype "passive"))
    )
    (net (code "44") (name "/P11") (class "Default")
      (node (ref "B1") (pin "11") (pinfunction "11_11") (pintype "bidirectional"))
      (node (ref "R2") (pin "P$1") (pinfunction "1_P$1") (pintype "passive"))
    )
    (net (code "45") (name "/P12") (class "Default")
      (node (ref "B1") (pin "12") (pinfunction "12_12") (pintype "bidirectional"))
      (node (ref "R3") (pin "P$1") (pinfunction "1_P$1") (pintype "passive"))
    )
    (net (code "46") (name "/P13") (class "Default")
      (node (ref "B1") (pin "13") (pinfunction "13_13") (pintype "bidirectional"))
      (node (ref "R4") (pin "P$1") (pinfunction "1_P$1") (pintype "passive"))
    )
    (net (code "47") (name "/P44") (class "Default")
      (node (ref "B1") (pin "44") (pinfunction "44_44") (pintype "bidirectional"))
      (node (ref "R13") (pin "P$1") (pinfunction "1_P$1") (pintype "passive"))
    )
    (net (code "48") (name "/P45") (class "Default")
      (node (ref "B1") (pin "45") (pinfunction "45_45") (pintype "bidirectional"))
      (node (ref "R14") (pin "P$1") (pinfunction "1_P$1") (pintype "passive"))
    )
    (net (code "49") (name "/P46") (class "Default")
      (node (ref "B1") (pin "46") (pinfunction "46_46") (pintype "bidirectional"))
      (node (ref "R15") (pin "P$1") (pinfunction "1_P$1") (pintype "passive"))
    )
    (net (code "50") (name "/PRX") (class "Default")
      (node (ref "B1") (pin "0") (pinfunction "0(RX0)_0") (pintype "bidirectional"))
      (node (ref "OK1") (pin "6") (pinfunction "VO_6") (pintype "passive"))
      (node (ref "R17") (pin "P$2") (pinfunction "2_P$2") (pintype "passive"))
    )
    (net (code "51") (name "/PTX") (class "Default")
      (node (ref "B1") (pin "1") (pinfunction "1(TX0)_1") (pintype "bidirectional"))
      (node (ref "XOUT") (pin "3") (pinfunction "KL_3") (pintype "passive"))
    )
    (net (code "52") (name "GND") (class "Default")
      (node (ref "B1") (pin "GND@0") (pinfunction "GND_GND@0") (pintype "bidirectional"))
      (node (ref "B1") (pin "GND@1") (pinfunction "GND_GND@1") (pintype "bidirectional"))
      (node (ref "B1") (pin "GND@2") (pinfunction "GND_GND@2") (pintype "bidirectional"))
      (node (ref "B1") (pin "GND@3") (pinfunction "GND_GND@3") (pintype "bidirectional"))
      (node (ref "C11") (pin "2") (pinfunction "2_2") (pintype "passive"))
      (node (ref "C12") (pin "1") (pinfunction "1_1") (pintype "passive"))
      (node (ref "C14") (pin "2") (pinfunction "2_2") (pintype "passive"))
      (node (ref "C15") (pin "1") (pinfunction "1_1") (pintype "passive"))
      (node (ref "C17") (pin "2") (pinfunction "2_2") (pintype "passive"))
      (node (ref "C18") (pin "1") (pinfunction "1_1") (pintype "passive"))
      (node (ref "C2") (pin "2") (pinfunction "2_2") (pintype "passive"))
      (node (ref "C20") (pin "2") (pinfunction "2_2") (pintype "passive"))
      (node (ref "C21") (pin "1") (pinfunction "1_1") (pintype "passive"))
      (node (ref "C23") (pin "2") (pinfunction "2_2") (pintype "passive"))
      (node (ref "C24") (pin "1") (pinfunction "1_1") (pintype "passive"))
      (node (ref "C26") (pin "2") (pinfunction "2_2") (pintype "passive"))
      (node (ref "C27") (pin "1") (pinfunction "1_1") (pintype "passive"))
      (node (ref "C29") (pin "2") (pinfunction "2_2") (pintype "passive"))
      (node (ref "C3") (pin "1") (pinfunction "1_1") (pintype "passive"))
      (node (ref "C30") (pin "1") (pinfunction "1_1") (pintype "passive"))
      (node (ref "C32") (pin "2") (pinfunction "2_2") (pintype "passive"))
      (node (ref "C33") (pin "1") (pinfunction "1_1") (pintype "passive"))
      (node (ref "C35") (pin "2") (pinfunction "2_2") (pintype "passive"))
      (node (ref "C36") (pin "1") (pinfunction "1_1") (pintype "passive"))
      (node (ref "C38") (pin "2") (pinfunction "2_2") (pintype "passive"))
      (node (ref "C39") (pin "1") (pinfunction "1_1") (pintype "passive"))
      (node (ref "C41") (pin "2") (pinfunction "2_2") (pintype "passive"))
      (node (ref "C42") (pin "1") (pinfunction "1_1") (pintype "passive"))
      (node (ref "C44") (pin "2") (pinfunction "2_2") (pintype "passive"))
      (node (ref "C45") (pin "1") (pinfunction "1_1") (pintype "passive"))
      (node (ref "C5") (pin "2") (pinfunction "2_2") (pintype "passive"))
      (node (ref "C6") (pin "1") (pinfunction "1_1") (pintype "passive"))
      (node (ref "C8") (pin "2") (pinfunction "2_2") (pintype "passive"))
      (node (ref "C9") (pin "1") (pinfunction "1_1") (pintype "passive"))
      (node (ref "IC1") (pin "GND") (pinfunction "GND_GND") (pintype "input"))
      (node (ref "IC10") (pin "GND") (pinfunction "GND_GND") (pintype "input"))
      (node (ref "IC11") (pin "GND") (pinfunction "GND_GND") (pintype "input"))
      (node (ref "IC12") (pin "GND") (pinfunction "GND_GND") (pintype "input"))
      (node (ref "IC13") (pin "GND") (pinfunction "GND_GND") (pintype "input"))
      (node (ref "IC14") (pin "GND") (pinfunction "GND_GND") (pintype "input"))
      (node (ref "IC15") (pin "GND") (pinfunction "GND_GND") (pintype "input"))
      (node (ref "IC2") (pin "GND") (pinfunction "GND_GND") (pintype "input"))
      (node (ref "IC3") (pin "GND") (pinfunction "GND_GND") (pintype "input"))
      (node (ref "IC4") (pin "GND") (pinfunction "GND_GND") (pintype "input"))
      (node (ref "IC5") (pin "GND") (pinfunction "GND_GND") (pintype "input"))
      (node (ref "IC6") (pin "GND") (pinfunction "GND_GND") (pintype "input"))
      (node (ref "IC7") (pin "GND") (pinfunction "GND_GND") (pintype "input"))
      (node (ref "IC8") (pin "GND") (pinfunction "GND_GND") (pintype "input"))
      (node (ref "IC9") (pin "GND") (pinfunction "GND_GND") (pintype "input"))
      (node (ref "OK1") (pin "5") (pinfunction "GND_5") (pintype "passive"))
      (node (ref "PWRIN") (pin "2") (pinfunction "KL_2") (pintype "passive"))
      (node (ref "PWROUT") (pin "2") (pinfunction "KL_2") (pintype "passive"))
      (node (ref "Q1") (pin "S") (pinfunction "S_S") (pintype "passive"))
      (node (ref "Q10") (pin "E") (pinfunction "E_E") (pintype "passive"))
      (node (ref "Q11") (pin "E") (pinfunction "E_E") (pintype "passive"))
      (node (ref "Q12") (pin "E") (pinfunction "E_E") (pintype "passive"))
      (node (ref "Q13") (pin "E") (pinfunction "E_E") (pintype "passive"))
      (node (ref "Q14") (pin "E") (pinfunction "E_E") (pintype "passive"))
      (node (ref "Q15") (pin "E") (pinfunction "E_E") (pintype "passive"))
      (node (ref "Q2") (pin "S") (pinfunction "S_S") (pintype "passive"))
      (node (ref "Q3") (pin "S") (pinfunction "S_S") (pintype "passive"))
      (node (ref "Q4") (pin "S") (pinfunction "S_S") (pintype "passive"))
      (node (ref "Q5") (pin "S") (pinfunction "S_S") (pintype "passive"))
      (node (ref "Q6") (pin "S") (pinfunction "S_S") (pintype "passive"))
      (node (ref "Q7") (pin "S") (pinfunction "S_S") (pintype "passive"))
      (node (ref "Q8") (pin "S") (pinfunction "S_S") (pintype "passive"))
      (node (ref "Q9") (pin "E") (pinfunction "E_E") (pintype "passive"))
      (node (ref "R18") (pin "P$2") (pinfunction "2_P$2") (pintype "passive"))
      (node (ref "XOUT") (pin "1") (pinfunction "KL_1") (pintype "passive"))
    )
    (net (code "53") (name "Net-(OK1-A)") (class "Default")
      (node (ref "D16") (pin "C") (pinfunction "C_C") (pintype "passive"))
      (node (ref "OK1") (pin "2") (pinfunction "A_2") (pintype "passive"))
      (node (ref "R16") (pin "P$1") (pinfunction "1_P$1") (pintype "passive"))
    )
    (net (code "54") (name "Net-(OK1-C)") (class "Default")
      (node (ref "D16") (pin "A") (pinfunction "A_A") (pintype "passive"))
      (node (ref "OK1") (pin "3") (pinfunction "C_3") (pintype "passive"))
      (node (ref "XIN") (pin "3") (pinfunction "KL_3") (pintype "passive"))
    )
    (net (code "55") (name "Net-(OK1-VB)") (class "Default")
      (node (ref "OK1") (pin "7") (pinfunction "VB_7") (pintype "passive"))
      (node (ref "R18") (pin "P$1") (pinfunction "1_P$1") (pintype "passive"))
    )
    (net (code "56") (name "Net-(R1-2)") (class "Default")
      (node (ref "Q1") (pin "G") (pinfunction "G_G") (pintype "passive"))
      (node (ref "R1") (pin "P$2") (pinfunction "2_P$2") (pintype "passive"))
    )
    (net (code "57") (name "Net-(R2-2)") (class "Default")
      (node (ref "Q2") (pin "G") (pinfunction "G_G") (pintype "passive"))
      (node (ref "R2") (pin "P$2") (pinfunction "2_P$2") (pintype "passive"))
    )
    (net (code "58") (name "Net-(R3-2)") (class "Default")
      (node (ref "Q3") (pin "G") (pinfunction "G_G") (pintype "passive"))
      (node (ref "R3") (pin "P$2") (pinfunction "2_P$2") (pintype "passive"))
    )
    (net (code "59") (name "Net-(R4-2)") (class "Default")
      (node (ref "Q4") (pin "G") (pinfunction "G_G") (pintype "passive"))
      (node (ref "R4") (pin "P$2") (pinfunction "2_P$2") (pintype "passive"))
    )
    (net (code "60") (name "Net-(R5-2)") (class "Default")
      (node (ref "Q5") (pin "G") (pinfunction "G_G") (pintype "passive"))
      (node (ref "R5") (pin "P$2") (pinfunction "2_P$2") (pintype "passive"))
    )
    (net (code "61") (name "Net-(R6-2)") (class "Default")
      (node (ref "Q6") (pin "G") (pinfunction "G_G") (pintype "passive"))
      (node (ref "R6") (pin "P$2") (pinfunction "2_P$2") (pintype "passive"))
    )
    (net (code "62") (name "Net-(R7-2)") (class "Default")
      (node (ref "Q7") (pin "G") (pinfunction "G_G") (pintype "passive"))
      (node (ref "R7") (pin "P$2") (pinfunction "2_P$2") (pintype "passive"))
    )
    (net (code "63") (name "Net-(R8-2)") (class "Default")
      (node (ref "Q8") (pin "G") (pinfunction "G_G") (pintype "passive"))
      (node (ref "R8") (pin "P$2") (pinfunction "2_P$2") (pintype "passive"))
    )
    (net (code "64") (name "Net-(R9-2)") (class "Default")
      (node (ref "Q9") (pin "B") (pinfunction "B_B") (pintype "passive"))
      (node (ref "R9") (pin "P$2") (pinfunction "2_P$2") (pintype "passive"))
    )
    (net (code "65") (name "Net-(R10-2)") (class "Default")
      (node (ref "Q10") (pin "B") (pinfunction "B_B") (pintype "passive"))
      (node (ref "R10") (pin "P$2") (pinfunction "2_P$2") (pintype "passive"))
    )
    (net (code "66") (name "Net-(R11-2)") (class "Default")
      (node (ref "Q11") (pin "B") (pinfunction "B_B") (pintype "passive"))
      (node (ref "R11") (pin "P$2") (pinfunction "2_P$2") (pintype "passive"))
    )
    (net (code "67") (name "Net-(R12-2)") (class "Default")
      (node (ref "Q12") (pin "B") (pinfunction "B_B") (pintype "passive"))
      (node (ref "R12") (pin "P$2") (pinfunction "2_P$2") (pintype "passive"))
    )
    (net (code "68") (name "Net-(R13-2)") (class "Default")
      (node (ref "Q13") (pin "B") (pinfunction "B_B") (pintype "passive"))
      (node (ref "R13") (pin "P$2") (pinfunction "2_P$2") (pintype "passive"))
    )
    (net (code "69") (name "Net-(R14-2)") (class "Default")
      (node (ref "Q14") (pin "B") (pinfunction "B_B") (pintype "passive"))
      (node (ref "R14") (pin "P$2") (pinfunction "2_P$2") (pintype "passive"))
    )
    (net (code "70") (name "Net-(R15-2)") (class "Default")
      (node (ref "Q15") (pin "B") (pinfunction "B_B") (pintype "passive"))
      (node (ref "R15") (pin "P$2") (pinfunction "2_P$2") (pintype "passive"))
    )
    (net (code "71") (name "Net-(R16-2)") (class "Default")
      (node (ref "R16") (pin "P$2") (pinfunction "2_P$2") (pintype "passive"))
      (node (ref "XIN") (pin "2") (pinfunction "KL_2") (pintype "passive"))
    )
    (net (code "72") (name "Net-(R19-2)") (class "Default")
      (node (ref "R19") (pin "P$2") (pinfunction "2_P$2") (pintype "passive"))
      (node (ref "XOUT") (pin "2") (pinfunction "KL_2") (pintype "passive"))
    )
    (net (code "73") (name "unconnected-(B1-5V-Pad5V@0)") (class "Default")
      (node (ref "B1") (pin "5V@0") (pinfunction "5V_5V@0") (pintype "bidirectional"))
    )
    (net (code "74") (name "unconnected-(B1-GND-PadGND@4)") (class "Default")
      (node (ref "B1") (pin "GND@4") (pinfunction "GND_GND@4") (pintype "bidirectional"))
    )
    (net (code "75") (name "unconnected-(B1-Pad3.3V)") (class "Default")
      (node (ref "B1") (pin "3.3V") (pinfunction "3.3V_3.3V") (pintype "bidirectional"))
    )
    (net (code "76") (name "unconnected-(B1-Pad47)") (class "Default")
      (node (ref "B1") (pin "47") (pinfunction "47_47") (pintype "bidirectional"))
    )
    (net (code "77") (name "unconnected-(B1-PadAREF)") (class "Default")
      (node (ref "B1") (pin "AREF") (pinfunction "AREF_AREF") (pintype "bidirectional"))
    )
    (net (code "78") (name "unconnected-(B1-PadRESET)") (class "Default")
      (node (ref "B1") (pin "RESET") (pinfunction "RESET_RESET") (pintype "bidirectional"))
    )
    (net (code "79") (name "unconnected-(D-Pad7)") (class "Default")
      (node (ref "D") (pin "7") (pinfunction "7_7") (pintype "bidirectional"))
    )
    (net (code "80") (name "unconnected-(D-Pad8)") (class "Default")
      (node (ref "D") (pin "8") (pinfunction "8_8") (pintype "bidirectional"))
    )
    (net (code "81") (name "unconnected-(XINA-KL-Pad1)") (class "Default")
      (node (ref "XIN") (pin "1") (pinfunction "KL_1") (pintype "passive"))
    )
  )
)
